# diode2.net
KiCad netlist of a schematic drawn in EAGLE
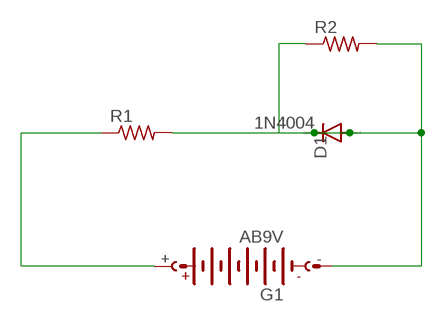
[diagram p0: schematic, sheet 1]

(export (version "E")
  (design (tool "Eeschema 10.0.6"))
  (components
    (comp (ref "D1")
      (value "1N4004")
      (footprint "eagle-import:DO41-10")
      (libsource (lib "eagle-import") (part "1N4004"))
    )
    (comp (ref "G1")
      (value "AB9V")
      (footprint "eagle-import:AB9V")
      (libsource (lib "eagle-import") (part "AB9V"))
    )
    (comp (ref "R1")
      (value "R-US_R0805")
      (footprint "eagle-import:R0805")
      (libsource (lib "eagle-import") (part "R-US_R0805"))
    )
    (comp (ref "R2")
      (value "R-US_R0805")
      (footprint "eagle-import:R0805")
      (libsource (lib "eagle-import") (part "R-US_R0805"))
    )
  )
  (nets
    (net (code "1") (name "Net-(D1-PadA)") (class "Default")
      (node (ref "D1") (pin "A") (pinfunction "A_A") (pintype "passive"))
      (node (ref "D1") (pin "C") (pinfunction "C_C") (pintype "passive"))
      (node (ref "G1") (pin "-") (pinfunction "-_-") (pintype "passive"))
      (node (ref "R1") (pin "2") (pinfunction "2_2") (pintype "passive"))
      (node (ref "R2") (pin "1") (pinfunction "1_1") (pintype "passive"))
      (node (ref "R2") (pin "2") (pinfunction "2_2") (pintype "passive"))
    )
    (net (code "2") (name "Net-(G1-Pad+)") (class "Default")
      (node (ref "G1") (pin "+") (pinfunction "+_+") (pintype "passive"))
      (node (ref "R1") (pin "1") (pinfunction "1_1") (pintype "passive"))
    )
  )
)
